# Led_matrix.net
KiCad netlist of a schematic drawn in EAGLE
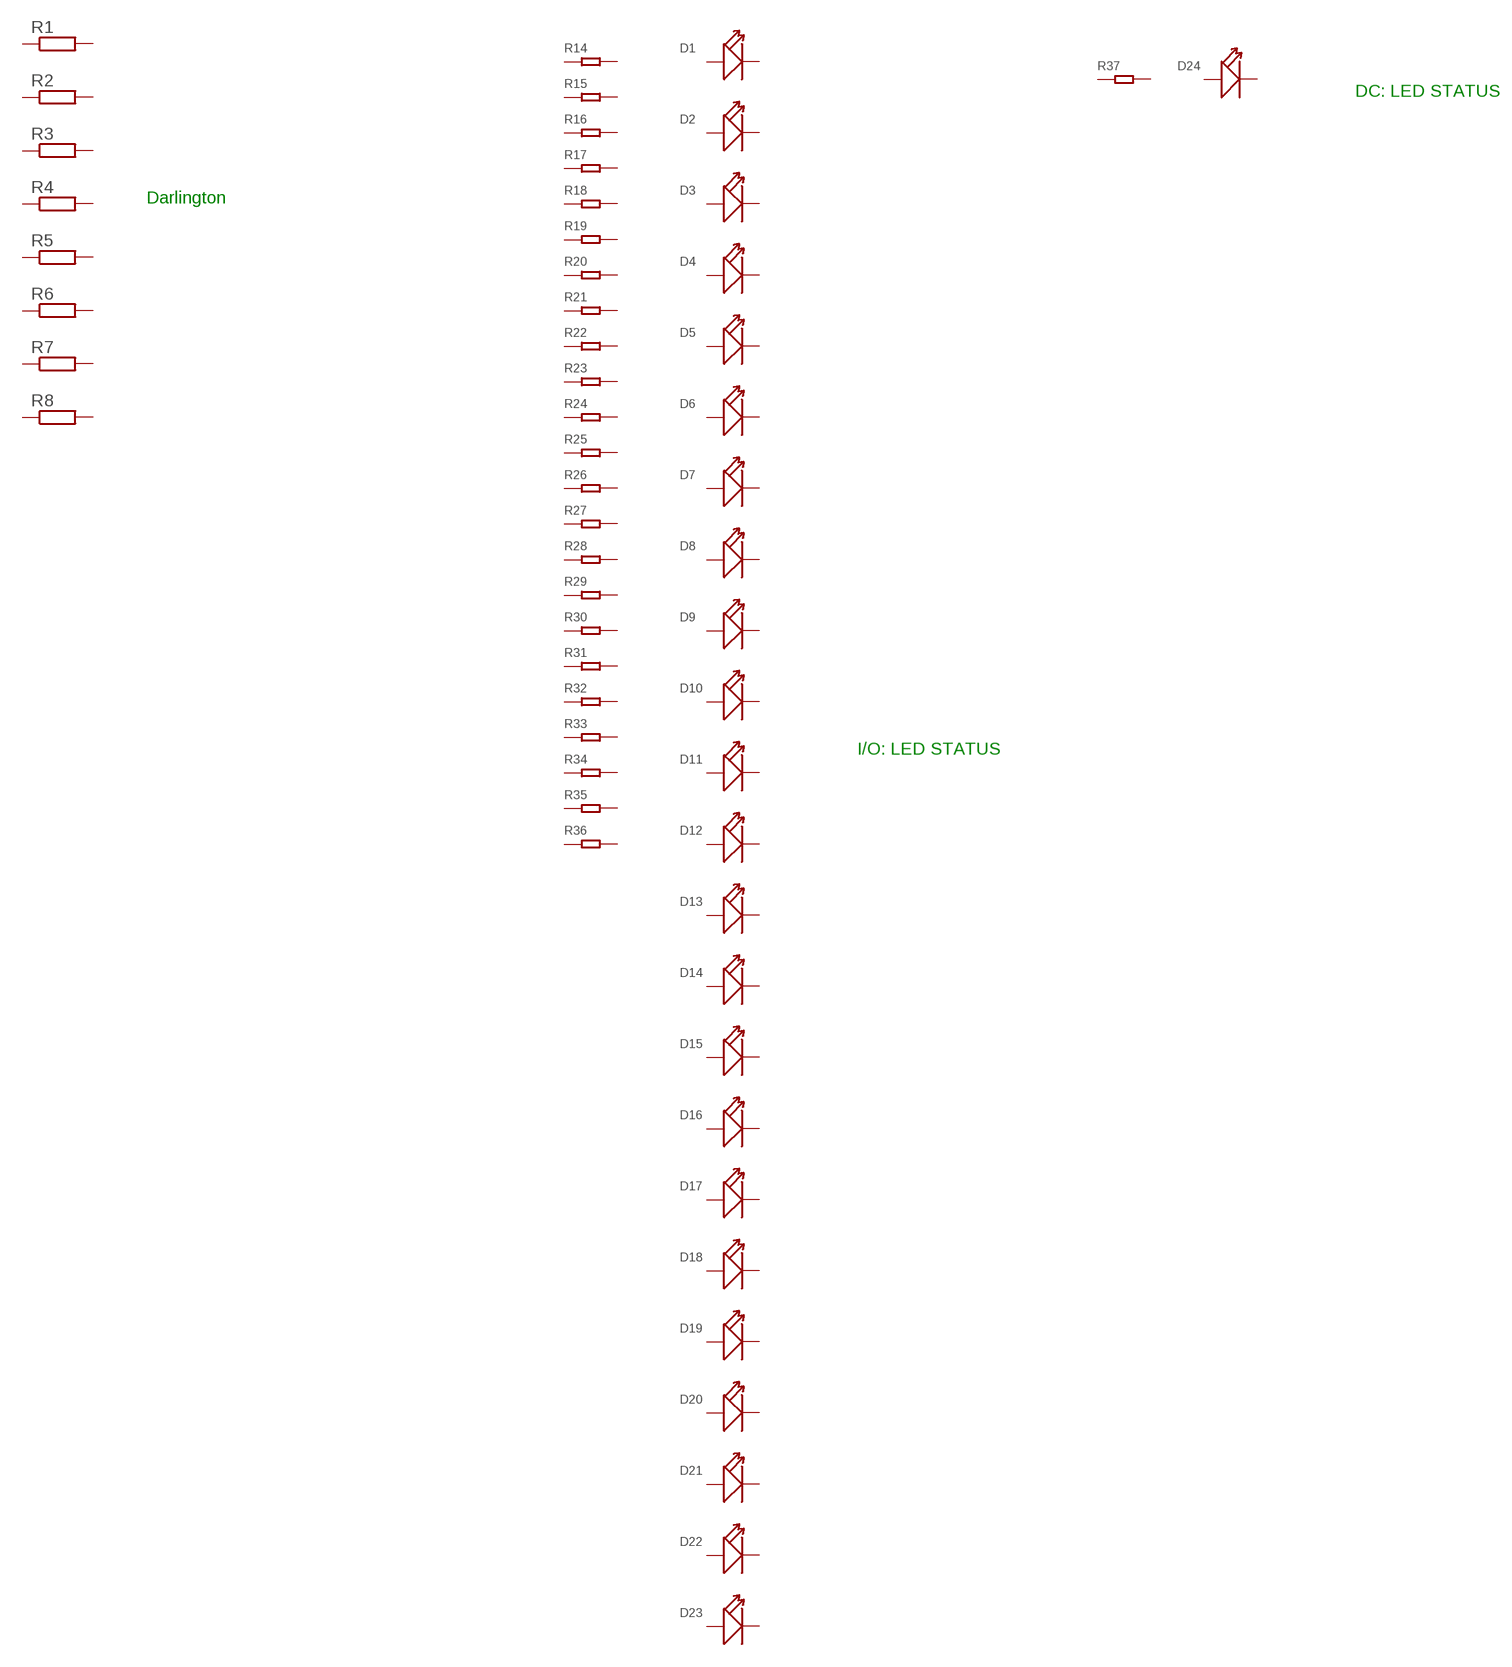
[diagram p0: schematic, sheet 1, part 1 of 2]
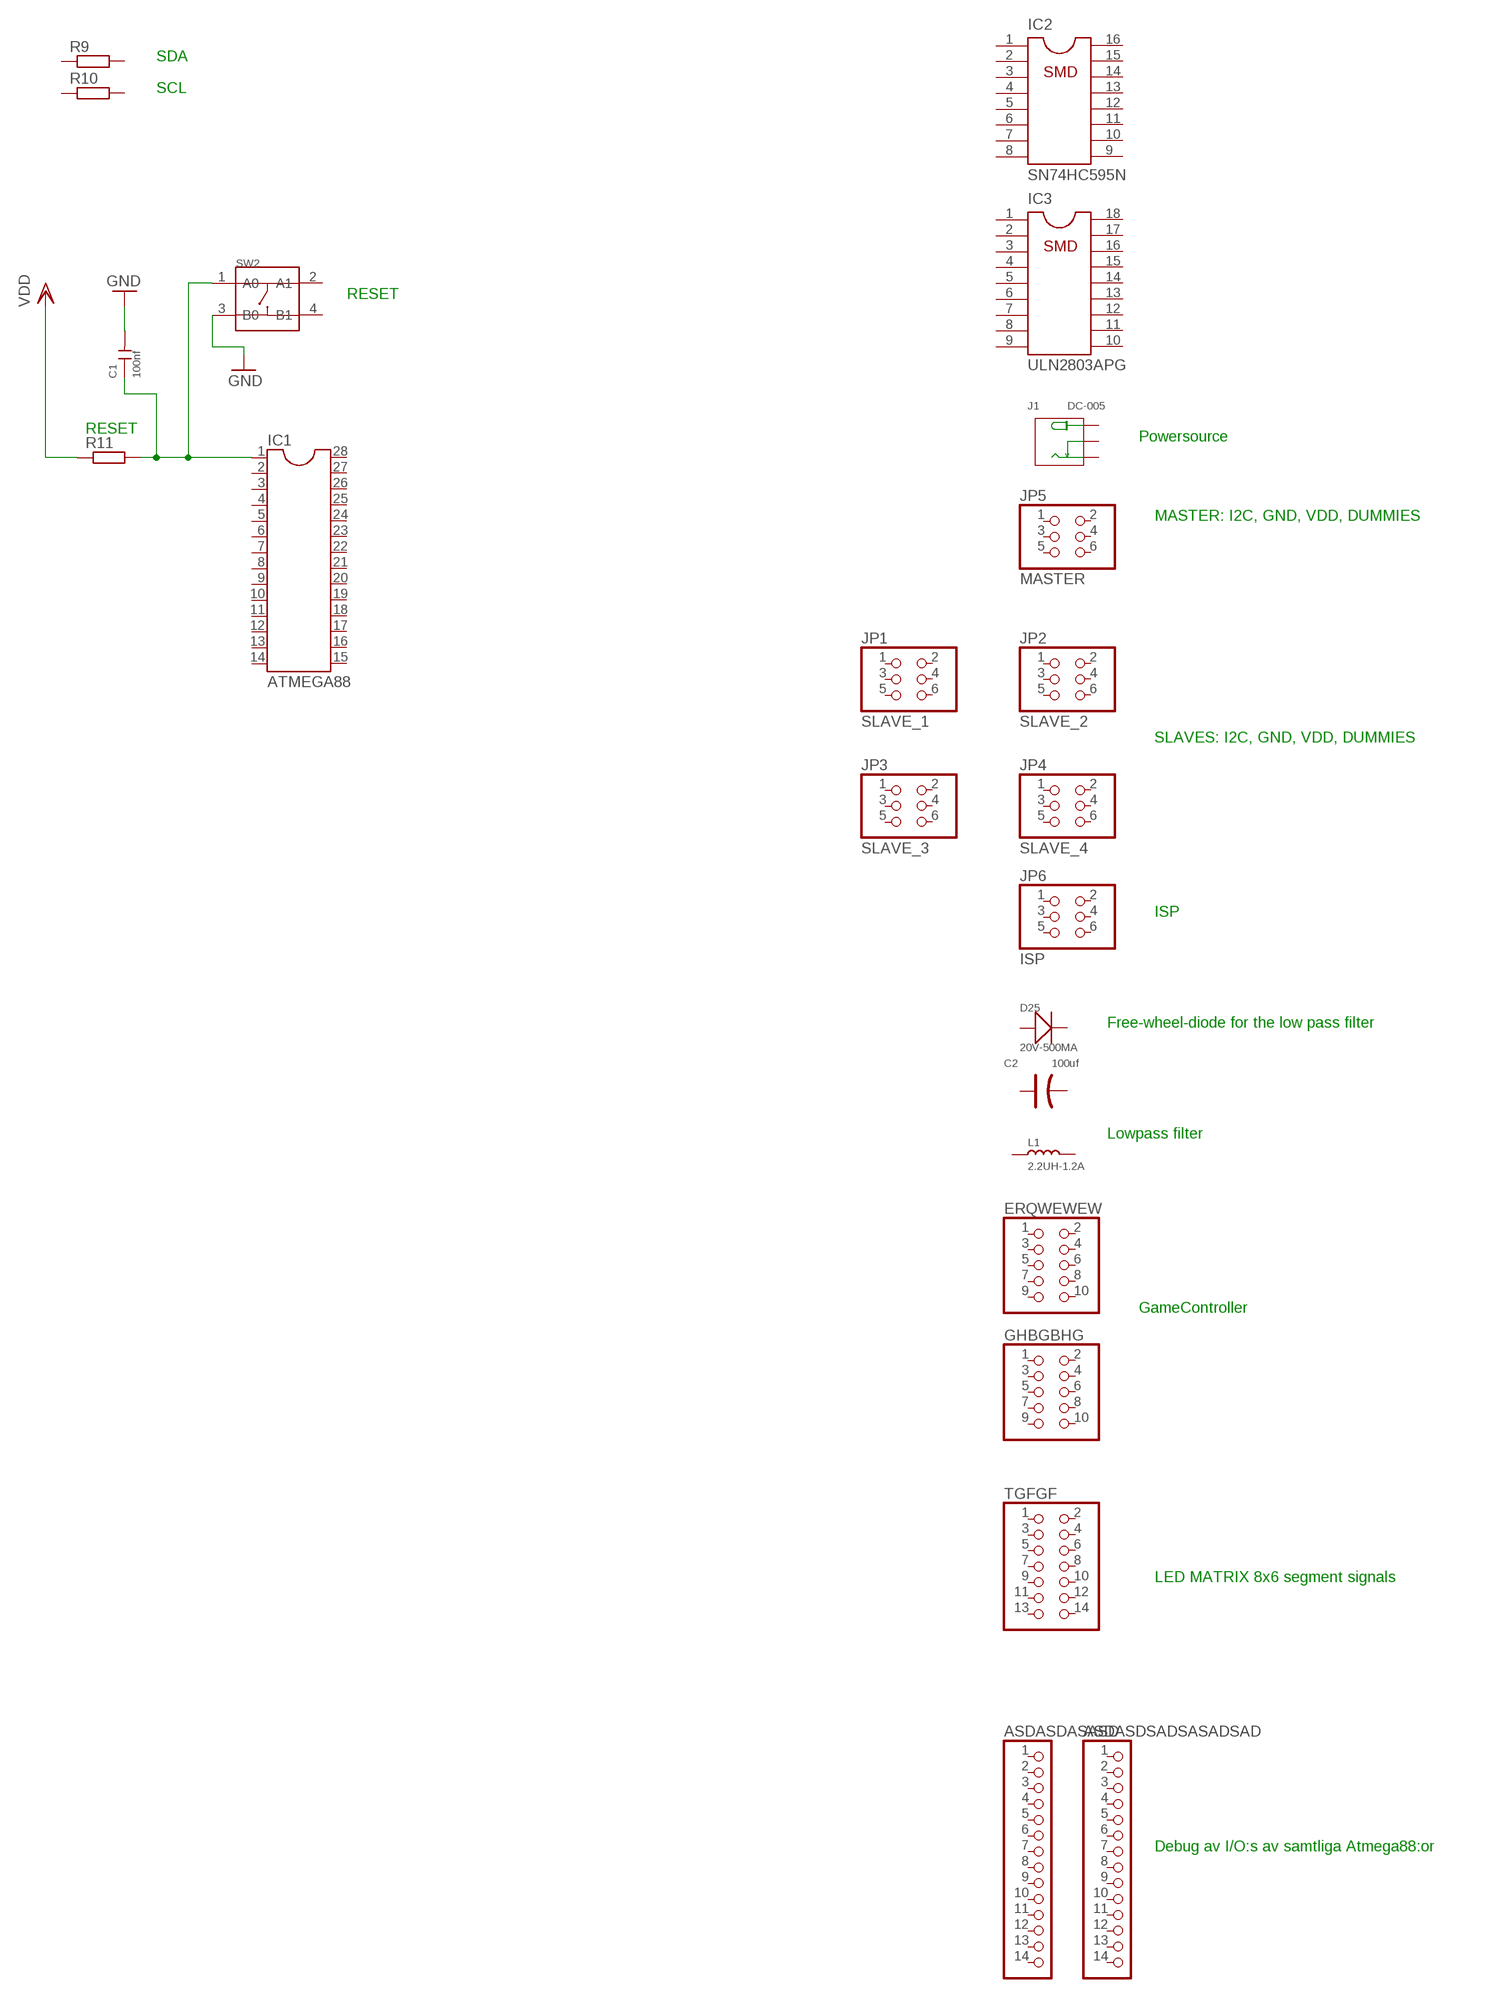
[diagram p1: schematic, sheet 1, part 2 of 2]

(export (version "E")
  (design (tool "Eeschema 10.0.6"))
  (components
    (comp (ref "ASDASDASASD")
      (value "PINHD-1X14")
      (footprint "eagle-import:1X14")
      (libsource (lib "eagle-import") (part "PINHD-1X14"))
    )
    (comp (ref "ASDASDSADSASADSAD")
      (value "PINHD-1X14")
      (footprint "eagle-import:1X14")
      (libsource (lib "eagle-import") (part "PINHD-1X14"))
    )
    (comp (ref "C1")
      (value "100nf")
      (footprint "eagle-import:CERAMIC-2.54")
      (fields (field (name "MPN") "CC1-F5SL2A101KSPW"))
      (libsource (lib "eagle-import") (part "DIP-CERAMIC-DISC-100NF-50V-Y5V(D5.0MM)"))
    )
    (comp (ref "C2")
      (value "100uf")
      (footprint "eagle-import:PC-D5.3MM")
      (libsource (lib "eagle-import") (part "DIP-ALUMINUM-100UF-16V(D5-H7MM)"))
    )
    (comp (ref "D1")
      (value "SMD-LED-CLEAR-GREEN(0603)")
      (footprint "eagle-import:LED-0603")
      (fields (field (name "MPN") "19-217-G7C-AN1P2-3T"))
      (libsource (lib "eagle-import") (part "SMD-LED-CLEAR-GREEN(0603)"))
    )
    (comp (ref "D2")
      (value "SMD-LED-CLEAR-GREEN(0603)")
      (footprint "eagle-import:LED-0603")
      (fields (field (name "MPN") "19-217-G7C-AN1P2-3T"))
      (libsource (lib "eagle-import") (part "SMD-LED-CLEAR-GREEN(0603)"))
    )
    (comp (ref "D3")
      (value "SMD-LED-CLEAR-GREEN(0603)")
      (footprint "eagle-import:LED-0603")
      (fields (field (name "MPN") "19-217-G7C-AN1P2-3T"))
      (libsource (lib "eagle-import") (part "SMD-LED-CLEAR-GREEN(0603)"))
    )
    (comp (ref "D4")
      (value "SMD-LED-CLEAR-GREEN(0603)")
      (footprint "eagle-import:LED-0603")
      (fields (field (name "MPN") "19-217-G7C-AN1P2-3T"))
      (libsource (lib "eagle-import") (part "SMD-LED-CLEAR-GREEN(0603)"))
    )
    (comp (ref "D5")
      (value "SMD-LED-CLEAR-GREEN(0603)")
      (footprint "eagle-import:LED-0603")
      (fields (field (name "MPN") "19-217-G7C-AN1P2-3T"))
      (libsource (lib "eagle-import") (part "SMD-LED-CLEAR-GREEN(0603)"))
    )
    (comp (ref "D6")
      (value "SMD-LED-CLEAR-GREEN(0603)")
      (footprint "eagle-import:LED-0603")
      (fields (field (name "MPN") "19-217-G7C-AN1P2-3T"))
      (libsource (lib "eagle-import") (part "SMD-LED-CLEAR-GREEN(0603)"))
    )
    (comp (ref "D7")
      (value "SMD-LED-CLEAR-GREEN(0603)")
      (footprint "eagle-import:LED-0603")
      (fields (field (name "MPN") "19-217-G7C-AN1P2-3T"))
      (libsource (lib "eagle-import") (part "SMD-LED-CLEAR-GREEN(0603)"))
    )
    (comp (ref "D8")
      (value "SMD-LED-CLEAR-GREEN(0603)")
      (footprint "eagle-import:LED-0603")
      (fields (field (name "MPN") "19-217-G7C-AN1P2-3T"))
      (libsource (lib "eagle-import") (part "SMD-LED-CLEAR-GREEN(0603)"))
    )
    (comp (ref "D9")
      (value "SMD-LED-CLEAR-GREEN(0603)")
      (footprint "eagle-import:LED-0603")
      (fields (field (name "MPN") "19-217-G7C-AN1P2-3T"))
      (libsource (lib "eagle-import") (part "SMD-LED-CLEAR-GREEN(0603)"))
    )
    (comp (ref "D10")
      (value "SMD-LED-CLEAR-GREEN(0603)")
      (footprint "eagle-import:LED-0603")
      (fields (field (name "MPN") "19-217-G7C-AN1P2-3T"))
      (libsource (lib "eagle-import") (part "SMD-LED-CLEAR-GREEN(0603)"))
    )
    (comp (ref "D11")
      (value "SMD-LED-CLEAR-GREEN(0603)")
      (footprint "eagle-import:LED-0603")
      (fields (field (name "MPN") "19-217-G7C-AN1P2-3T"))
      (libsource (lib "eagle-import") (part "SMD-LED-CLEAR-GREEN(0603)"))
    )
    (comp (ref "D12")
      (value "SMD-LED-CLEAR-GREEN(0603)")
      (footprint "eagle-import:LED-0603")
      (fields (field (name "MPN") "19-217-G7C-AN1P2-3T"))
      (libsource (lib "eagle-import") (part "SMD-LED-CLEAR-GREEN(0603)"))
    )
    (comp (ref "D13")
      (value "SMD-LED-CLEAR-GREEN(0603)")
      (footprint "eagle-import:LED-0603")
      (fields (field (name "MPN") "19-217-G7C-AN1P2-3T"))
      (libsource (lib "eagle-import") (part "SMD-LED-CLEAR-GREEN(0603)"))
    )
    (comp (ref "D14")
      (value "SMD-LED-CLEAR-GREEN(0603)")
      (footprint "eagle-import:LED-0603")
      (fields (field (name "MPN") "19-217-G7C-AN1P2-3T"))
      (libsource (lib "eagle-import") (part "SMD-LED-CLEAR-GREEN(0603)"))
    )
    (comp (ref "D15")
      (value "SMD-LED-CLEAR-GREEN(0603)")
      (footprint "eagle-import:LED-0603")
      (fields (field (name "MPN") "19-217-G7C-AN1P2-3T"))
      (libsource (lib "eagle-import") (part "SMD-LED-CLEAR-GREEN(0603)"))
    )
    (comp (ref "D16")
      (value "SMD-LED-CLEAR-GREEN(0603)")
      (footprint "eagle-import:LED-0603")
      (fields (field (name "MPN") "19-217-G7C-AN1P2-3T"))
      (libsource (lib "eagle-import") (part "SMD-LED-CLEAR-GREEN(0603)"))
    )
    (comp (ref "D17")
      (value "SMD-LED-CLEAR-GREEN(0603)")
      (footprint "eagle-import:LED-0603")
      (fields (field (name "MPN") "19-217-G7C-AN1P2-3T"))
      (libsource (lib "eagle-import") (part "SMD-LED-CLEAR-GREEN(0603)"))
    )
    (comp (ref "D18")
      (value "SMD-LED-CLEAR-GREEN(0603)")
      (footprint "eagle-import:LED-0603")
      (fields (field (name "MPN") "19-217-G7C-AN1P2-3T"))
      (libsource (lib "eagle-import") (part "SMD-LED-CLEAR-GREEN(0603)"))
    )
    (comp (ref "D19")
      (value "SMD-LED-CLEAR-GREEN(0603)")
      (footprint "eagle-import:LED-0603")
      (fields (field (name "MPN") "19-217-G7C-AN1P2-3T"))
      (libsource (lib "eagle-import") (part "SMD-LED-CLEAR-GREEN(0603)"))
    )
    (comp (ref "D20")
      (value "SMD-LED-CLEAR-GREEN(0603)")
      (footprint "eagle-import:LED-0603")
      (fields (field (name "MPN") "19-217-G7C-AN1P2-3T"))
      (libsource (lib "eagle-import") (part "SMD-LED-CLEAR-GREEN(0603)"))
    )
    (comp (ref "D21")
      (value "SMD-LED-CLEAR-GREEN(0603)")
      (footprint "eagle-import:LED-0603")
      (fields (field (name "MPN") "19-217-G7C-AN1P2-3T"))
      (libsource (lib "eagle-import") (part "SMD-LED-CLEAR-GREEN(0603)"))
    )
    (comp (ref "D22")
      (value "SMD-LED-CLEAR-GREEN(0603)")
      (footprint "eagle-import:LED-0603")
      (fields (field (name "MPN") "19-217-G7C-AN1P2-3T"))
      (libsource (lib "eagle-import") (part "SMD-LED-CLEAR-GREEN(0603)"))
    )
    (comp (ref "D23")
      (value "SMD-LED-CLEAR-GREEN(0603)")
      (footprint "eagle-import:LED-0603")
      (fields (field (name "MPN") "19-217-G7C-AN1P2-3T"))
      (libsource (lib "eagle-import") (part "SMD-LED-CLEAR-GREEN(0603)"))
    )
    (comp (ref "D24")
      (value "SMD-LED-CLEAR-GREEN(0603)")
      (footprint "eagle-import:LED-0603")
      (fields (field (name "MPN") "19-217-G7C-AN1P2-3T"))
      (libsource (lib "eagle-import") (part "SMD-LED-CLEAR-GREEN(0603)"))
    )
    (comp (ref "D25")
      (value "20V-500MA")
      (footprint "eagle-import:SOD-123")
      (fields (field (name "MPN") "SS0520-7-F"))
      (libsource (lib "eagle-import") (part "SMD-DIODE-SCHOTTKY-20V-500MA(SOD-123)P"))
    )
    (comp (ref "ERQWEWEW")
      (value "PINHD-2X5")
      (footprint "eagle-import:2X05")
      (libsource (lib "eagle-import") (part "PINHD-2X5"))
    )
    (comp (ref "GHBGBHG")
      (value "PINHD-2X5")
      (footprint "eagle-import:2X05")
      (libsource (lib "eagle-import") (part "PINHD-2X5"))
    )
    (comp (ref "IC1")
      (value "ATMEGA88")
      (footprint "eagle-import:DIL28-3")
      (libsource (lib "eagle-import") (part "DIL28-3"))
    )
    (comp (ref "IC2")
      (value "SN74HC595N")
      (footprint "eagle-import:DIL16-SMD")
      (libsource (lib "eagle-import") (part "DIL16-SMD"))
    )
    (comp (ref "IC3")
      (value "ULN2803APG")
      (footprint "eagle-import:DIL18-SMD")
      (libsource (lib "eagle-import") (part "DIL18-SMD"))
    )
    (comp (ref "J1")
      (value "DC-005")
      (footprint "eagle-import:DCJ3P-14.2X11.0X9.0MM")
      (libsource (lib "eagle-import") (part "CONN-POWER-JACK-2.1MM(DC-005)"))
    )
    (comp (ref "JP1")
      (value "SLAVE_1")
      (footprint "eagle-import:2X03-SMD")
      (libsource (lib "eagle-import") (part "PINHD-2X3-SMD"))
    )
    (comp (ref "JP2")
      (value "SLAVE_2")
      (footprint "eagle-import:2X03-SMD")
      (libsource (lib "eagle-import") (part "PINHD-2X3-SMD"))
    )
    (comp (ref "JP3")
      (value "SLAVE_3")
      (footprint "eagle-import:2X03-SMD")
      (libsource (lib "eagle-import") (part "PINHD-2X3-SMD"))
    )
    (comp (ref "JP4")
      (value "SLAVE_4")
      (footprint "eagle-import:2X03-SMD")
      (libsource (lib "eagle-import") (part "PINHD-2X3-SMD"))
    )
    (comp (ref "JP5")
      (value "MASTER")
      (footprint "eagle-import:2X03-SMD")
      (libsource (lib "eagle-import") (part "PINHD-2X3-SMD"))
    )
    (comp (ref "JP6")
      (value "ISP")
      (footprint "eagle-import:2X03-SHROUDED")
      (libsource (lib "eagle-import") (part "PINHD-2X3-SHROUDED"))
    )
    (comp (ref "L1")
      (value "2.2UH-1.2A")
      (footprint "eagle-import:L0805")
      (fields (field (name "MPN") "LQM2MPN2R2MG0"))
      (libsource (lib "eagle-import") (part "SMD-INDUCTOR-2.2UH-20%-1.2A(0805)"))
    )
    (comp (ref "R1")
      (value "R-EU_0411/15")
      (footprint "eagle-import:0411_15")
      (libsource (lib "eagle-import") (part "R-EU_0411/15"))
    )
    (comp (ref "R2")
      (value "R-EU_0411/15")
      (footprint "eagle-import:0411_15")
      (libsource (lib "eagle-import") (part "R-EU_0411/15"))
    )
    (comp (ref "R3")
      (value "R-EU_0411/15")
      (footprint "eagle-import:0411_15")
      (libsource (lib "eagle-import") (part "R-EU_0411/15"))
    )
    (comp (ref "R4")
      (value "R-EU_0411/15")
      (footprint "eagle-import:0411_15")
      (libsource (lib "eagle-import") (part "R-EU_0411/15"))
    )
    (comp (ref "R5")
      (value "R-EU_0411/15")
      (footprint "eagle-import:0411_15")
      (libsource (lib "eagle-import") (part "R-EU_0411/15"))
    )
    (comp (ref "R6")
      (value "R-EU_0411/15")
      (footprint "eagle-import:0411_15")
      (libsource (lib "eagle-import") (part "R-EU_0411/15"))
    )
    (comp (ref "R7")
      (value "R-EU_0411/15")
      (footprint "eagle-import:0411_15")
      (libsource (lib "eagle-import") (part "R-EU_0411/15"))
    )
    (comp (ref "R8")
      (value "R-EU_0411/15")
      (footprint "eagle-import:0411_15")
      (libsource (lib "eagle-import") (part "R-EU_0411/15"))
    )
    (comp (ref "R9")
      (value "R-EU_0207/10")
      (footprint "eagle-import:0207_10")
      (libsource (lib "eagle-import") (part "R-EU_0207/10"))
    )
    (comp (ref "R10")
      (value "R-EU_0207/10")
      (footprint "eagle-import:0207_10")
      (libsource (lib "eagle-import") (part "R-EU_0207/10"))
    )
    (comp (ref "R11")
      (value "R-EU_0207/10")
      (footprint "eagle-import:0207_10")
      (libsource (lib "eagle-import") (part "R-EU_0207/10"))
    )
    (comp (ref "R14")
      (value "SMD-RES-100R-5%-1/10W(0603)")
      (footprint "eagle-import:R0603")
      (fields (field (name "MPN") "RC0603JR-07100RL"))
      (libsource (lib "eagle-import") (part "SMD-RES-100R-5%-1/10W(0603)"))
    )
    (comp (ref "R15")
      (value "SMD-RES-100R-5%-1/10W(0603)")
      (footprint "eagle-import:R0603")
      (fields (field (name "MPN") "RC0603JR-07100RL"))
      (libsource (lib "eagle-import") (part "SMD-RES-100R-5%-1/10W(0603)"))
    )
    (comp (ref "R16")
      (value "SMD-RES-100R-5%-1/10W(0603)")
      (footprint "eagle-import:R0603")
      (fields (field (name "MPN") "RC0603JR-07100RL"))
      (libsource (lib "eagle-import") (part "SMD-RES-100R-5%-1/10W(0603)"))
    )
    (comp (ref "R17")
      (value "SMD-RES-100R-5%-1/10W(0603)")
      (footprint "eagle-import:R0603")
      (fields (field (name "MPN") "RC0603JR-07100RL"))
      (libsource (lib "eagle-import") (part "SMD-RES-100R-5%-1/10W(0603)"))
    )
    (comp (ref "R18")
      (value "SMD-RES-100R-5%-1/10W(0603)")
      (footprint "eagle-import:R0603")
      (fields (field (name "MPN") "RC0603JR-07100RL"))
      (libsource (lib "eagle-import") (part "SMD-RES-100R-5%-1/10W(0603)"))
    )
    (comp (ref "R19")
      (value "SMD-RES-100R-5%-1/10W(0603)")
      (footprint "eagle-import:R0603")
      (fields (field (name "MPN") "RC0603JR-07100RL"))
      (libsource (lib "eagle-import") (part "SMD-RES-100R-5%-1/10W(0603)"))
    )
    (comp (ref "R20")
      (value "SMD-RES-100R-5%-1/10W(0603)")
      (footprint "eagle-import:R0603")
      (fields (field (name "MPN") "RC0603JR-07100RL"))
      (libsource (lib "eagle-import") (part "SMD-RES-100R-5%-1/10W(0603)"))
    )
    (comp (ref "R21")
      (value "SMD-RES-100R-5%-1/10W(0603)")
      (footprint "eagle-import:R0603")
      (fields (field (name "MPN") "RC0603JR-07100RL"))
      (libsource (lib "eagle-import") (part "SMD-RES-100R-5%-1/10W(0603)"))
    )
    (comp (ref "R22")
      (value "SMD-RES-100R-5%-1/10W(0603)")
      (footprint "eagle-import:R0603")
      (fields (field (name "MPN") "RC0603JR-07100RL"))
      (libsource (lib "eagle-import") (part "SMD-RES-100R-5%-1/10W(0603)"))
    )
    (comp (ref "R23")
      (value "SMD-RES-100R-5%-1/10W(0603)")
      (footprint "eagle-import:R0603")
      (fields (field (name "MPN") "RC0603JR-07100RL"))
      (libsource (lib "eagle-import") (part "SMD-RES-100R-5%-1/10W(0603)"))
    )
    (comp (ref "R24")
      (value "SMD-RES-100R-5%-1/10W(0603)")
      (footprint "eagle-import:R0603")
      (fields (field (name "MPN") "RC0603JR-07100RL"))
      (libsource (lib "eagle-import") (part "SMD-RES-100R-5%-1/10W(0603)"))
    )
    (comp (ref "R25")
      (value "SMD-RES-100R-5%-1/10W(0603)")
      (footprint "eagle-import:R0603")
      (fields (field (name "MPN") "RC0603JR-07100RL"))
      (libsource (lib "eagle-import") (part "SMD-RES-100R-5%-1/10W(0603)"))
    )
    (comp (ref "R26")
      (value "SMD-RES-100R-5%-1/10W(0603)")
      (footprint "eagle-import:R0603")
      (fields (field (name "MPN") "RC0603JR-07100RL"))
      (libsource (lib "eagle-import") (part "SMD-RES-100R-5%-1/10W(0603)"))
    )
    (comp (ref "R27")
      (value "SMD-RES-100R-5%-1/10W(0603)")
      (footprint "eagle-import:R0603")
      (fields (field (name "MPN") "RC0603JR-07100RL"))
      (libsource (lib "eagle-import") (part "SMD-RES-100R-5%-1/10W(0603)"))
    )
    (comp (ref "R28")
      (value "SMD-RES-100R-5%-1/10W(0603)")
      (footprint "eagle-import:R0603")
      (fields (field (name "MPN") "RC0603JR-07100RL"))
      (libsource (lib "eagle-import") (part "SMD-RES-100R-5%-1/10W(0603)"))
    )
    (comp (ref "R29")
      (value "SMD-RES-100R-5%-1/10W(0603)")
      (footprint "eagle-import:R0603")
      (fields (field (name "MPN") "RC0603JR-07100RL"))
      (libsource (lib "eagle-import") (part "SMD-RES-100R-5%-1/10W(0603)"))
    )
    (comp (ref "R30")
      (value "SMD-RES-100R-5%-1/10W(0603)")
      (footprint "eagle-import:R0603")
      (fields (field (name "MPN") "RC0603JR-07100RL"))
      (libsource (lib "eagle-import") (part "SMD-RES-100R-5%-1/10W(0603)"))
    )
    (comp (ref "R31")
      (value "SMD-RES-100R-5%-1/10W(0603)")
      (footprint "eagle-import:R0603")
      (fields (field (name "MPN") "RC0603JR-07100RL"))
      (libsource (lib "eagle-import") (part "SMD-RES-100R-5%-1/10W(0603)"))
    )
    (comp (ref "R32")
      (value "SMD-RES-100R-5%-1/10W(0603)")
      (footprint "eagle-import:R0603")
      (fields (field (name "MPN") "RC0603JR-07100RL"))
      (libsource (lib "eagle-import") (part "SMD-RES-100R-5%-1/10W(0603)"))
    )
    (comp (ref "R33")
      (value "SMD-RES-100R-5%-1/10W(0603)")
      (footprint "eagle-import:R0603")
      (fields (field (name "MPN") "RC0603JR-07100RL"))
      (libsource (lib "eagle-import") (part "SMD-RES-100R-5%-1/10W(0603)"))
    )
    (comp (ref "R34")
      (value "SMD-RES-100R-5%-1/10W(0603)")
      (footprint "eagle-import:R0603")
      (fields (field (name "MPN") "RC0603JR-07100RL"))
      (libsource (lib "eagle-import") (part "SMD-RES-100R-5%-1/10W(0603)"))
    )
    (comp (ref "R35")
      (value "SMD-RES-100R-5%-1/10W(0603)")
      (footprint "eagle-import:R0603")
      (fields (field (name "MPN") "RC0603JR-07100RL"))
      (libsource (lib "eagle-import") (part "SMD-RES-100R-5%-1/10W(0603)"))
    )
    (comp (ref "R36")
      (value "SMD-RES-100R-5%-1/10W(0603)")
      (footprint "eagle-import:R0603")
      (fields (field (name "MPN") "RC0603JR-07100RL"))
      (libsource (lib "eagle-import") (part "SMD-RES-100R-5%-1/10W(0603)"))
    )
    (comp (ref "R37")
      (value "SMD-RES-100R-5%-1/10W(0603)")
      (footprint "eagle-import:R0603")
      (fields (field (name "MPN") "RC0603JR-07100RL"))
      (libsource (lib "eagle-import") (part "SMD-RES-100R-5%-1/10W(0603)"))
    )
    (comp (ref "SW2")
      (value "SMD-BUTTON(4P-6.0X6.0X7.5MM)")
      (footprint "eagle-import:SW4-4.5-6.0X6.0X7.5MM")
      (libsource (lib "eagle-import") (part "SMD-BUTTON(4P-6.0X6.0X7.5MM)"))
    )
    (comp (ref "TGFGF")
      (value "PINHD-2X7")
      (footprint "eagle-import:2X07")
      (libsource (lib "eagle-import") (part "PINHD-2X7"))
    )
  )
  (nets
    (net (code "1") (name "GND") (class "Default")
      (node (ref "C1") (pin "2") (pinfunction "2_2") (pintype "passive"))
      (node (ref "SW2") (pin "3") (pinfunction "B0_3") (pintype "bidirectional"))
    )
    (net (code "2") (name "Net-(SW2-A0)") (class "Default")
      (node (ref "C1") (pin "1") (pinfunction "1_1") (pintype "passive"))
      (node (ref "IC1") (pin "1") (pinfunction "1_1") (pintype "passive"))
      (node (ref "R11") (pin "2") (pinfunction "2_2") (pintype "passive"))
      (node (ref "SW2") (pin "1") (pinfunction "A0_1") (pintype "bidirectional"))
    )
    (net (code "3") (name "VDD") (class "Default")
      (node (ref "R11") (pin "1") (pinfunction "1_1") (pintype "passive"))
    )
    (net (code "4") (name "unconnected-(ASDASDASASD-Pad1)") (class "Default")
      (node (ref "ASDASDASASD") (pin "1") (pinfunction "1_1") (pintype "passive"))
    )
    (net (code "5") (name "unconnected-(ASDASDASASD-Pad2)") (class "Default")
      (node (ref "ASDASDASASD") (pin "2") (pinfunction "2_2") (pintype "passive"))
    )
    (net (code "6") (name "unconnected-(ASDASDASASD-Pad3)") (class "Default")
      (node (ref "ASDASDASASD") (pin "3") (pinfunction "3_3") (pintype "passive"))
    )
    (net (code "7") (name "unconnected-(ASDASDASASD-Pad4)") (class "Default")
      (node (ref "ASDASDASASD") (pin "4") (pinfunction "4_4") (pintype "passive"))
    )
    (net (code "8") (name "unconnected-(ASDASDASASD-Pad5)") (class "Default")
      (node (ref "ASDASDASASD") (pin "5") (pinfunction "5_5") (pintype "passive"))
    )
    (net (code "9") (name "unconnected-(ASDASDASASD-Pad6)") (class "Default")
      (node (ref "ASDASDASASD") (pin "6") (pinfunction "6_6") (pintype "passive"))
    )
    (net (code "10") (name "unconnected-(ASDASDASASD-Pad7)") (class "Default")
      (node (ref "ASDASDASASD") (pin "7") (pinfunction "7_7") (pintype "passive"))
    )
    (net (code "11") (name "unconnected-(ASDASDASASD-Pad8)") (class "Default")
      (node (ref "ASDASDASASD") (pin "8") (pinfunction "8_8") (pintype "passive"))
    )
    (net (code "12") (name "unconnected-(ASDASDASASD-Pad9)") (class "Default")
      (node (ref "ASDASDASASD") (pin "9") (pinfunction "9_9") (pintype "passive"))
    )
    (net (code "13") (name "unconnected-(ASDASDASASD-Pad10)") (class "Default")
      (node (ref "ASDASDASASD") (pin "10") (pinfunction "10_10") (pintype "passive"))
    )
    (net (code "14") (name "unconnected-(ASDASDASASD-Pad11)") (class "Default")
      (node (ref "ASDASDASASD") (pin "11") (pinfunction "11_11") (pintype "passive"))
    )
    (net (code "15") (name "unconnected-(ASDASDASASD-Pad12)") (class "Default")
      (node (ref "ASDASDASASD") (pin "12") (pinfunction "12_12") (pintype "passive"))
    )
    (net (code "16") (name "unconnected-(ASDASDASASD-Pad13)") (class "Default")
      (node (ref "ASDASDASASD") (pin "13") (pinfunction "13_13") (pintype "passive"))
    )
    (net (code "17") (name "unconnected-(ASDASDASASD-Pad14)") (class "Default")
      (node (ref "ASDASDASASD") (pin "14") (pinfunction "14_14") (pintype "passive"))
    )
    (net (code "18") (name "unconnected-(ASDASDSADSASADSAD-Pad1)") (class "Default")
      (node (ref "ASDASDSADSASADSAD") (pin "1") (pinfunction "1_1") (pintype "passive"))
    )
    (net (code "19") (name "unconnected-(ASDASDSADSASADSAD-Pad2)") (class "Default")
      (node (ref "ASDASDSADSASADSAD") (pin "2") (pinfunction "2_2") (pintype "passive"))
    )
    (net (code "20") (name "unconnected-(ASDASDSADSASADSAD-Pad3)") (class "Default")
      (node (ref "ASDASDSADSASADSAD") (pin "3") (pinfunction "3_3") (pintype "passive"))
    )
    (net (code "21") (name "unconnected-(ASDASDSADSASADSAD-Pad4)") (class "Default")
      (node (ref "ASDASDSADSASADSAD") (pin "4") (pinfunction "4_4") (pintype "passive"))
    )
    (net (code "22") (name "unconnected-(ASDASDSADSASADSAD-Pad5)") (class "Default")
      (node (ref "ASDASDSADSASADSAD") (pin "5") (pinfunction "5_5") (pintype "passive"))
    )
    (net (code "23") (name "unconnected-(ASDASDSADSASADSAD-Pad6)") (class "Default")
      (node (ref "ASDASDSADSASADSAD") (pin "6") (pinfunction "6_6") (pintype "passive"))
    )
    (net (code "24") (name "unconnected-(ASDASDSADSASADSAD-Pad7)") (class "Default")
      (node (ref "ASDASDSADSASADSAD") (pin "7") (pinfunction "7_7") (pintype "passive"))
    )
    (net (code "25") (name "unconnected-(ASDASDSADSASADSAD-Pad8)") (class "Default")
      (node (ref "ASDASDSADSASADSAD") (pin "8") (pinfunction "8_8") (pintype "passive"))
    )
    (net (code "26") (name "unconnected-(ASDASDSADSASADSAD-Pad9)") (class "Default")
      (node (ref "ASDASDSADSASADSAD") (pin "9") (pinfunction "9_9") (pintype "passive"))
    )
    (net (code "27") (name "unconnected-(ASDASDSADSASADSAD-Pad10)") (class "Default")
      (node (ref "ASDASDSADSASADSAD") (pin "10") (pinfunction "10_10") (pintype "passive"))
    )
    (net (code "28") (name "unconnected-(ASDASDSADSASADSAD-Pad11)") (class "Default")
      (node (ref "ASDASDSADSASADSAD") (pin "11") (pinfunction "11_11") (pintype "passive"))
    )
    (net (code "29") (name "unconnected-(ASDASDSADSASADSAD-Pad12)") (class "Default")
      (node (ref "ASDASDSADSASADSAD") (pin "12") (pinfunction "12_12") (pintype "passive"))
    )
    (net (code "30") (name "unconnected-(ASDASDSADSASADSAD-Pad13)") (class "Default")
      (node (ref "ASDASDSADSASADSAD") (pin "13") (pinfunction "13_13") (pintype "passive"))
    )
    (net (code "31") (name "unconnected-(ASDASDSADSASADSAD-Pad14)") (class "Default")
      (node (ref "ASDASDSADSASADSAD") (pin "14") (pinfunction "14_14") (pintype "passive"))
    )
    (net (code "32") (name "unconnected-(C2-Pad+)") (class "Default")
      (node (ref "C2") (pin "+") (pinfunction "+_+") (pintype "passive"))
    )
    (net (code "33") (name "unconnected-(C2-Pad-)") (class "Default")
      (node (ref "C2") (pin "-") (pinfunction "-_-") (pintype "passive"))
    )
    (net (code "34") (name "unconnected-(D1-Pad+)") (class "Default")
      (node (ref "D1") (pin "+") (pinfunction "+_+") (pintype "passive"))
    )
    (net (code "35") (name "unconnected-(D1-Pad-)") (class "Default")
      (node (ref "D1") (pin "-") (pinfunction "-_-") (pintype "passive"))
    )
    (net (code "36") (name "unconnected-(D2-Pad+)") (class "Default")
      (node (ref "D2") (pin "+") (pinfunction "+_+") (pintype "passive"))
    )
    (net (code "37") (name "unconnected-(D2-Pad-)") (class "Default")
      (node (ref "D2") (pin "-") (pinfunction "-_-") (pintype "passive"))
    )
    (net (code "38") (name "unconnected-(D3-Pad+)") (class "Default")
      (node (ref "D3") (pin "+") (pinfunction "+_+") (pintype "passive"))
    )
    (net (code "39") (name "unconnected-(D3-Pad-)") (class "Default")
      (node (ref "D3") (pin "-") (pinfunction "-_-") (pintype "passive"))
    )
    (net (code "40") (name "unconnected-(D4-Pad+)") (class "Default")
      (node (ref "D4") (pin "+") (pinfunction "+_+") (pintype "passive"))
    )
    (net (code "41") (name "unconnected-(D4-Pad-)") (class "Default")
      (node (ref "D4") (pin "-") (pinfunction "-_-") (pintype "passive"))
    )
    (net (code "42") (name "unconnected-(D5-Pad+)") (class "Default")
      (node (ref "D5") (pin "+") (pinfunction "+_+") (pintype "passive"))
    )
    (net (code "43") (name "unconnected-(D5-Pad-)") (class "Default")
      (node (ref "D5") (pin "-") (pinfunction "-_-") (pintype "passive"))
    )
    (net (code "44") (name "unconnected-(D6-Pad+)") (class "Default")
      (node (ref "D6") (pin "+") (pinfunction "+_+") (pintype "passive"))
    )
    (net (code "45") (name "unconnected-(D6-Pad-)") (class "Default")
      (node (ref "D6") (pin "-") (pinfunction "-_-") (pintype "passive"))
    )
    (net (code "46") (name "unconnected-(D7-Pad+)") (class "Default")
      (node (ref "D7") (pin "+") (pinfunction "+_+") (pintype "passive"))
    )
    (net (code "47") (name "unconnected-(D7-Pad-)") (class "Default")
      (node (ref "D7") (pin "-") (pinfunction "-_-") (pintype "passive"))
    )
    (net (code "48") (name "unconnected-(D8-Pad+)") (class "Default")
      (node (ref "D8") (pin "+") (pinfunction "+_+") (pintype "passive"))
    )
    (net (code "49") (name "unconnected-(D8-Pad-)") (class "Default")
      (node (ref "D8") (pin "-") (pinfunction "-_-") (pintype "passive"))
    )
    (net (code "50") (name "unconnected-(D9-Pad+)") (class "Default")
      (node (ref "D9") (pin "+") (pinfunction "+_+") (pintype "passive"))
    )
    (net (code "51") (name "unconnected-(D9-Pad-)") (class "Default")
      (node (ref "D9") (pin "-") (pinfunction "-_-") (pintype "passive"))
    )
    (net (code "52") (name "unconnected-(D10-Pad+)") (class "Default")
      (node (ref "D10") (pin "+") (pinfunction "+_+") (pintype "passive"))
    )
    (net (code "53") (name "unconnected-(D10-Pad-)") (class "Default")
      (node (ref "D10") (pin "-") (pinfunction "-_-") (pintype "passive"))
    )
    (net (code "54") (name "unconnected-(D11-Pad+)") (class "Default")
      (node (ref "D11") (pin "+") (pinfunction "+_+") (pintype "passive"))
    )
    (net (code "55") (name "unconnected-(D11-Pad-)") (class "Default")
      (node (ref "D11") (pin "-") (pinfunction "-_-") (pintype "passive"))
    )
    (net (code "56") (name "unconnected-(D12-Pad+)") (class "Default")
      (node (ref "D12") (pin "+") (pinfunction "+_+") (pintype "passive"))
    )
    (net (code "57") (name "unconnected-(D12-Pad-)") (class "Default")
      (node (ref "D12") (pin "-") (pinfunction "-_-") (pintype "passive"))
    )
    (net (code "58") (name "unconnected-(D13-Pad+)") (class "Default")
      (node (ref "D13") (pin "+") (pinfunction "+_+") (pintype "passive"))
    )
    (net (code "59") (name "unconnected-(D13-Pad-)") (class "Default")
      (node (ref "D13") (pin "-") (pinfunction "-_-") (pintype "passive"))
    )
    (net (code "60") (name "unconnected-(D14-Pad+)") (class "Default")
      (node (ref "D14") (pin "+") (pinfunction "+_+") (pintype "passive"))
    )
    (net (code "61") (name "unconnected-(D14-Pad-)") (class "Default")
      (node (ref "D14") (pin "-") (pinfunction "-_-") (pintype "passive"))
    )
    (net (code "62") (name "unconnected-(D15-Pad+)") (class "Default")
      (node (ref "D15") (pin "+") (pinfunction "+_+") (pintype "passive"))
    )
    (net (code "63") (name "unconnected-(D15-Pad-)") (class "Default")
      (node (ref "D15") (pin "-") (pinfunction "-_-") (pintype "passive"))
    )
    (net (code "64") (name "unconnected-(D16-Pad+)") (class "Default")
      (node (ref "D16") (pin "+") (pinfunction "+_+") (pintype "passive"))
    )
    (net (code "65") (name "unconnected-(D16-Pad-)") (class "Default")
      (node (ref "D16") (pin "-") (pinfunction "-_-") (pintype "passive"))
    )
    (net (code "66") (name "unconnected-(D17-Pad+)") (class "Default")
      (node (ref "D17") (pin "+") (pinfunction "+_+") (pintype "passive"))
    )
    (net (code "67") (name "unconnected-(D17-Pad-)") (class "Default")
      (node (ref "D17") (pin "-") (pinfunction "-_-") (pintype "passive"))
    )
    (net (code "68") (name "unconnected-(D18-Pad+)") (class "Default")
      (node (ref "D18") (pin "+") (pinfunction "+_+") (pintype "passive"))
    )
    (net (code "69") (name "unconnected-(D18-Pad-)") (class "Default")
      (node (ref "D18") (pin "-") (pinfunction "-_-") (pintype "passive"))
    )
    (net (code "70") (name "unconnected-(D19-Pad+)") (class "Default")
      (node (ref "D19") (pin "+") (pinfunction "+_+") (pintype "passive"))
    )
    (net (code "71") (name "unconnected-(D19-Pad-)") (class "Default")
      (node (ref "D19") (pin "-") (pinfunction "-_-") (pintype "passive"))
    )
    (net (code "72") (name "unconnected-(D20-Pad+)") (class "Default")
      (node (ref "D20") (pin "+") (pinfunction "+_+") (pintype "passive"))
    )
    (net (code "73") (name "unconnected-(D20-Pad-)") (class "Default")
      (node (ref "D20") (pin "-") (pinfunction "-_-") (pintype "passive"))
    )
    (net (code "74") (name "unconnected-(D21-Pad+)") (class "Default")
      (node (ref "D21") (pin "+") (pinfunction "+_+") (pintype "passive"))
    )
    (net (code "75") (name "unconnected-(D21-Pad-)") (class "Default")
      (node (ref "D21") (pin "-") (pinfunction "-_-") (pintype "passive"))
    )
    (net (code "76") (name "unconnected-(D22-Pad+)") (class "Default")
      (node (ref "D22") (pin "+") (pinfunction "+_+") (pintype "passive"))
    )
    (net (code "77") (name "unconnected-(D22-Pad-)") (class "Default")
      (node (ref "D22") (pin "-") (pinfunction "-_-") (pintype "passive"))
    )
    (net (code "78") (name "unconnected-(D23-Pad+)") (class "Default")
      (node (ref "D23") (pin "+") (pinfunction "+_+") (pintype "passive"))
    )
    (net (code "79") (name "unconnected-(D23-Pad-)") (class "Default")
      (node (ref "D23") (pin "-") (pinfunction "-_-") (pintype "passive"))
    )
    (net (code "80") (name "unconnected-(D24-Pad+)") (class "Default")
      (node (ref "D24") (pin "+") (pinfunction "+_+") (pintype "passive"))
    )
    (net (code "81") (name "unconnected-(D24-Pad-)") (class "Default")
      (node (ref "D24") (pin "-") (pinfunction "-_-") (pintype "passive"))
    )
    (net (code "82") (name "unconnected-(D25-Pad+)") (class "Default")
      (node (ref "D25") (pin "+") (pinfunction "+_+") (pintype "passive"))
    )
    (net (code "83") (name "unconnected-(D25-Pad-)") (class "Default")
      (node (ref "D25") (pin "-") (pinfunction "-_-") (pintype "passive"))
    )
    (net (code "84") (name "unconnected-(ERQWEWEW-Pad1)") (class "Default")
      (node (ref "ERQWEWEW") (pin "1") (pinfunction "1_1") (pintype "passive"))
    )
    (net (code "85") (name "unconnected-(ERQWEWEW-Pad2)") (class "Default")
      (node (ref "ERQWEWEW") (pin "2") (pinfunction "2_2") (pintype "passive"))
    )
    (net (code "86") (name "unconnected-(ERQWEWEW-Pad3)") (class "Default")
      (node (ref "ERQWEWEW") (pin "3") (pinfunction "3_3") (pintype "passive"))
    )
    (net (code "87") (name "unconnected-(ERQWEWEW-Pad4)") (class "Default")
      (node (ref "ERQWEWEW") (pin "4") (pinfunction "4_4") (pintype "passive"))
    )
    (net (code "88") (name "unconnected-(ERQWEWEW-Pad5)") (class "Default")
      (node (ref "ERQWEWEW") (pin "5") (pinfunction "5_5") (pintype "passive"))
    )
    (net (code "89") (name "unconnected-(ERQWEWEW-Pad6)") (class "Default")
      (node (ref "ERQWEWEW") (pin "6") (pinfunction "6_6") (pintype "passive"))
    )
    (net (code "90") (name "unconnected-(ERQWEWEW-Pad7)") (class "Default")
      (node (ref "ERQWEWEW") (pin "7") (pinfunction "7_7") (pintype "passive"))
    )
    (net (code "91") (name "unconnected-(ERQWEWEW-Pad8)") (class "Default")
      (node (ref "ERQWEWEW") (pin "8") (pinfunction "8_8") (pintype "passive"))
    )
    (net (code "92") (name "unconnected-(ERQWEWEW-Pad9)") (class "Default")
      (node (ref "ERQWEWEW") (pin "9") (pinfunction "9_9") (pintype "passive"))
    )
    (net (code "93") (name "unconnected-(ERQWEWEW-Pad10)") (class "Default")
      (node (ref "ERQWEWEW") (pin "10") (pinfunction "10_10") (pintype "passive"))
    )
    (net (code "94") (name "unconnected-(GHBGBHG-Pad1)") (class "Default")
      (node (ref "GHBGBHG") (pin "1") (pinfunction "1_1") (pintype "passive"))
    )
    (net (code "95") (name "unconnected-(GHBGBHG-Pad2)") (class "Default")
      (node (ref "GHBGBHG") (pin "2") (pinfunction "2_2") (pintype "passive"))
    )
    (net (code "96") (name "unconnected-(GHBGBHG-Pad3)") (class "Default")
      (node (ref "GHBGBHG") (pin "3") (pinfunction "3_3") (pintype "passive"))
    )
    (net (code "97") (name "unconnected-(GHBGBHG-Pad4)") (class "Default")
      (node (ref "GHBGBHG") (pin "4") (pinfunction "4_4") (pintype "passive"))
    )
    (net (code "98") (name "unconnected-(GHBGBHG-Pad5)") (class "Default")
      (node (ref "GHBGBHG") (pin "5") (pinfunction "5_5") (pintype "passive"))
    )
    (net (code "99") (name "unconnected-(GHBGBHG-Pad6)") (class "Default")
      (node (ref "GHBGBHG") (pin "6") (pinfunction "6_6") (pintype "passive"))
    )
    (net (code "100") (name "unconnected-(GHBGBHG-Pad7)") (class "Default")
      (node (ref "GHBGBHG") (pin "7") (pinfunction "7_7") (pintype "passive"))
    )
    (net (code "101") (name "unconnected-(GHBGBHG-Pad8)") (class "Default")
      (node (ref "GHBGBHG") (pin "8") (pinfunction "8_8") (pintype "passive"))
    )
    (net (code "102") (name "unconnected-(GHBGBHG-Pad9)") (class "Default")
      (node (ref "GHBGBHG") (pin "9") (pinfunction "9_9") (pintype "passive"))
    )
    (net (code "103") (name "unconnected-(GHBGBHG-Pad10)") (class "Default")
      (node (ref "GHBGBHG") (pin "10") (pinfunction "10_10") (pintype "passive"))
    )
    (net (code "104") (name "unconnected-(IC1-Pad2)") (class "Default")
      (node (ref "IC1") (pin "2") (pinfunction "2_2") (pintype "passive"))
    )
    (net (code "105") (name "unconnected-(IC1-Pad3)") (class "Default")
      (node (ref "IC1") (pin "3") (pinfunction "3_3") (pintype "passive"))
    )
    (net (code "106") (name "unconnected-(IC1-Pad4)") (class "Default")
      (node (ref "IC1") (pin "4") (pinfunction "4_4") (pintype "passive"))
    )
    (net (code "107") (name "unconnected-(IC1-Pad5)") (class "Default")
      (node (ref "IC1") (pin "5") (pinfunction "5_5") (pintype "passive"))
    )
    (net (code "108") (name "unconnected-(IC1-Pad6)") (class "Default")
      (node (ref "IC1") (pin "6") (pinfunction "6_6") (pintype "passive"))
    )
    (net (code "109") (name "unconnected-(IC1-Pad7)") (class "Default")
      (node (ref "IC1") (pin "7") (pinfunction "7_7") (pintype "passive"))
    )
    (net (code "110") (name "unconnected-(IC1-Pad8)") (class "Default")
      (node (ref "IC1") (pin "8") (pinfunction "8_8") (pintype "passive"))
    )
    (net (code "111") (name "unconnected-(IC1-Pad9)") (class "Default")
      (node (ref "IC1") (pin "9") (pinfunction "9_9") (pintype "passive"))
    )
    (net (code "112") (name "unconnected-(IC1-Pad10)") (class "Default")
      (node (ref "IC1") (pin "10") (pinfunction "10_10") (pintype "passive"))
    )
    (net (code "113") (name "unconnected-(IC1-Pad11)") (class "Default")
      (node (ref "IC1") (pin "11") (pinfunction "11_11") (pintype "passive"))
    )
    (net (code "114") (name "unconnected-(IC1-Pad12)") (class "Default")
      (node (ref "IC1") (pin "12") (pinfunction "12_12") (pintype "passive"))
    )
    (net (code "115") (name "unconnected-(IC1-Pad13)") (class "Default")
      (node (ref "IC1") (pin "13") (pinfunction "13_13") (pintype "passive"))
    )
    (net (code "116") (name "unconnected-(IC1-Pad14)") (class "Default")
      (node (ref "IC1") (pin "14") (pinfunction "14_14") (pintype "passive"))
    )
    (net (code "117") (name "unconnected-(IC1-Pad15)") (class "Default")
      (node (ref "IC1") (pin "15") (pinfunction "15_15") (pintype "passive"))
    )
    (net (code "118") (name "unconnected-(IC1-Pad16)") (class "Default")
      (node (ref "IC1") (pin "16") (pinfunction "16_16") (pintype "passive"))
    )
    (net (code "119") (name "unconnected-(IC1-Pad17)") (class "Default")
      (node (ref "IC1") (pin "17") (pinfunction "17_17") (pintype "passive"))
    )
    (net (code "120") (name "unconnected-(IC1-Pad18)") (class "Default")
      (node (ref "IC1") (pin "18") (pinfunction "18_18") (pintype "passive"))
    )
    (net (code "121") (name "unconnected-(IC1-Pad19)") (class "Default")
      (node (ref "IC1") (pin "19") (pinfunction "19_19") (pintype "passive"))
    )
    (net (code "122") (name "unconnected-(IC1-Pad20)") (class "Default")
      (node (ref "IC1") (pin "20") (pinfunction "20_20") (pintype "passive"))
    )
    (net (code "123") (name "unconnected-(IC1-Pad21)") (class "Default")
      (node (ref "IC1") (pin "21") (pinfunction "21_21") (pintype "passive"))
    )
    (net (code "124") (name "unconnected-(IC1-Pad22)") (class "Default")
      (node (ref "IC1") (pin "22") (pinfunction "22_22") (pintype "passive"))
    )
    (net (code "125") (name "unconnected-(IC1-Pad23)") (class "Default")
      (node (ref "IC1") (pin "23") (pinfunction "23_23") (pintype "passive"))
    )
    (net (code "126") (name "unconnected-(IC1-Pad24)") (class "Default")
      (node (ref "IC1") (pin "24") (pinfunction "24_24") (pintype "passive"))
    )
    (net (code "127") (name "unconnected-(IC1-Pad25)") (class "Default")
      (node (ref "IC1") (pin "25") (pinfunction "25_25") (pintype "passive"))
    )
    (net (code "128") (name "unconnected-(IC1-Pad26)") (class "Default")
      (node (ref "IC1") (pin "26") (pinfunction "26_26") (pintype "passive"))
    )
    (net (code "129") (name "unconnected-(IC1-Pad27)") (class "Default")
      (node (ref "IC1") (pin "27") (pinfunction "27_27") (pintype "passive"))
    )
    (net (code "130") (name "unconnected-(IC1-Pad28)") (class "Default")
      (node (ref "IC1") (pin "28") (pinfunction "28_28") (pintype "passive"))
    )
    (net (code "131") (name "unconnected-(IC2-Pad1)") (class "Default")
      (node (ref "IC2") (pin "1") (pinfunction "1_1") (pintype "bidirectional"))
    )
    (net (code "132") (name "unconnected-(IC2-Pad2)") (class "Default")
      (node (ref "IC2") (pin "2") (pinfunction "2_2") (pintype "bidirectional"))
    )
    (net (code "133") (name "unconnected-(IC2-Pad3)") (class "Default")
      (node (ref "IC2") (pin "3") (pinfunction "3_3") (pintype "bidirectional"))
    )
    (net (code "134") (name "unconnected-(IC2-Pad4)") (class "Default")
      (node (ref "IC2") (pin "4") (pinfunction "4_4") (pintype "bidirectional"))
    )
    (net (code "135") (name "unconnected-(IC2-Pad5)") (class "Default")
      (node (ref "IC2") (pin "5") (pinfunction "5_5") (pintype "bidirectional"))
    )
    (net (code "136") (name "unconnected-(IC2-Pad6)") (class "Default")
      (node (ref "IC2") (pin "6") (pinfunction "6_6") (pintype "bidirectional"))
    )
    (net (code "137") (name "unconnected-(IC2-Pad7)") (class "Default")
      (node (ref "IC2") (pin "7") (pinfunction "7_7") (pintype "bidirectional"))
    )
    (net (code "138") (name "unconnected-(IC2-Pad8)") (class "Default")
      (node (ref "IC2") (pin "8") (pinfunction "8_8") (pintype "bidirectional"))
    )
    (net (code "139") (name "unconnected-(IC2-Pad9)") (class "Default")
      (node (ref "IC2") (pin "9") (pinfunction "9_9") (pintype "bidirectional"))
    )
    (net (code "140") (name "unconnected-(IC2-Pad10)") (class "Default")
      (node (ref "IC2") (pin "10") (pinfunction "10_10") (pintype "bidirectional"))
    )
    (net (code "141") (name "unconnected-(IC2-Pad11)") (class "Default")
      (node (ref "IC2") (pin "11") (pinfunction "11_11") (pintype "bidirectional"))
    )
    (net (code "142") (name "unconnected-(IC2-Pad12)") (class "Default")
      (node (ref "IC2") (pin "12") (pinfunction "12_12") (pintype "bidirectional"))
    )
    (net (code "143") (name "unconnected-(IC2-Pad13)") (class "Default")
      (node (ref "IC2") (pin "13") (pinfunction "13_13") (pintype "bidirectional"))
    )
    (net (code "144") (name "unconnected-(IC2-Pad14)") (class "Default")
      (node (ref "IC2") (pin "14") (pinfunction "14_14") (pintype "bidirectional"))
    )
    (net (code "145") (name "unconnected-(IC2-Pad15)") (class "Default")
      (node (ref "IC2") (pin "15") (pinfunction "15_15") (pintype "bidirectional"))
    )
    (net (code "146") (name "unconnected-(IC2-Pad16)") (class "Default")
      (node (ref "IC2") (pin "16") (pinfunction "16_16") (pintype "bidirectional"))
    )
    (net (code "147") (name "unconnected-(IC3-P$1-Pad1)") (class "Default")
      (node (ref "IC3") (pin "1") (pinfunction "P$1_1") (pintype "bidirectional"))
    )
    (net (code "148") (name "unconnected-(IC3-P$2-Pad2)") (class "Default")
      (node (ref "IC3") (pin "2") (pinfunction "P$2_2") (pintype "bidirectional"))
    )
    (net (code "149") (name "unconnected-(IC3-P$3-Pad3)") (class "Default")
      (node (ref "IC3") (pin "3") (pinfunction "P$3_3") (pintype "bidirectional"))
    )
    (net (code "150") (name "unconnected-(IC3-P$4-Pad4)") (class "Default")
      (node (ref "IC3") (pin "4") (pinfunction "P$4_4") (pintype "bidirectional"))
    )
    (net (code "151") (name "unconnected-(IC3-P$5-Pad5)") (class "Default")
      (node (ref "IC3") (pin "5") (pinfunction "P$5_5") (pintype "bidirectional"))
    )
    (net (code "152") (name "unconnected-(IC3-P$6-Pad6)") (class "Default")
      (node (ref "IC3") (pin "6") (pinfunction "P$6_6") (pintype "bidirectional"))
    )
    (net (code "153") (name "unconnected-(IC3-P$7-Pad7)") (class "Default")
      (node (ref "IC3") (pin "7") (pinfunction "P$7_7") (pintype "bidirectional"))
    )
    (net (code "154") (name "unconnected-(IC3-P$8-Pad8)") (class "Default")
      (node (ref "IC3") (pin "8") (pinfunction "P$8_8") (pintype "bidirectional"))
    )
    (net (code "155") (name "unconnected-(IC3-P$9-Pad9)") (class "Default")
      (node (ref "IC3") (pin "9") (pinfunction "P$9_9") (pintype "bidirectional"))
    )
    (net (code "156") (name "unconnected-(IC3-P$10-Pad10)") (class "Default")
      (node (ref "IC3") (pin "10") (pinfunction "P$10_10") (pintype "bidirectional"))
    )
    (net (code "157") (name "unconnected-(IC3-P$11-Pad11)") (class "Default")
      (node (ref "IC3") (pin "11") (pinfunction "P$11_11") (pintype "bidirectional"))
    )
    (net (code "158") (name "unconnected-(IC3-P$12-Pad12)") (class "Default")
      (node (ref "IC3") (pin "12") (pinfunction "P$12_12") (pintype "bidirectional"))
    )
    (net (code "159") (name "unconnected-(IC3-P$13-Pad13)") (class "Default")
      (node (ref "IC3") (pin "13") (pinfunction "P$13_13") (pintype "bidirectional"))
    )
    (net (code "160") (name "unconnected-(IC3-P$14-Pad14)") (class "Default")
      (node (ref "IC3") (pin "14") (pinfunction "P$14_14") (pintype "bidirectional"))
    )
    (net (code "161") (name "unconnected-(IC3-P$15-Pad15)") (class "Default")
      (node (ref "IC3") (pin "15") (pinfunction "P$15_15") (pintype "bidirectional"))
    )
    (net (code "162") (name "unconnected-(IC3-P$16-Pad16)") (class "Default")
      (node (ref "IC3") (pin "16") (pinfunction "P$16_16") (pintype "bidirectional"))
    )
    (net (code "163") (name "unconnected-(IC3-P$17-Pad17)") (class "Default")
      (node (ref "IC3") (pin "17") (pinfunction "P$17_17") (pintype "bidirectional"))
    )
    (net (code "164") (name "unconnected-(IC3-P$18-Pad18)") (class "Default")
      (node (ref "IC3") (pin "18") (pinfunction "P$18_18") (pintype "bidirectional"))
    )
    (net (code "165") (name "unconnected-(J1---Pad-1)") (class "Default")
      (node (ref "J1") (pin "-1") (pinfunction "-_-1") (pintype "bidirectional"))
    )
    (net (code "166") (name "unconnected-(J1-CDN-Pad-2)") (class "Default")
      (node (ref "J1") (pin "-2") (pinfunction "CDN_-2") (pintype "bidirectional"))
    )
    (net (code "167") (name "unconnected-(J1-Pad+)") (class "Default")
      (node (ref "J1") (pin "+") (pinfunction "+_+") (pintype "bidirectional"))
    )
    (net (code "168") (name "unconnected-(JP1-Pad1)") (class "Default")
      (node (ref "JP1") (pin "1") (pinfunction "1_1") (pintype "passive"))
    )
    (net (code "169") (name "unconnected-(JP1-Pad2)") (class "Default")
      (node (ref "JP1") (pin "2") (pinfunction "2_2") (pintype "passive"))
    )
    (net (code "170") (name "unconnected-(JP1-Pad3)") (class "Default")
      (node (ref "JP1") (pin "3") (pinfunction "3_3") (pintype "passive"))
    )
    (net (code "171") (name "unconnected-(JP1-Pad4)") (class "Default")
      (node (ref "JP1") (pin "4") (pinfunction "4_4") (pintype "passive"))
    )
    (net (code "172") (name "unconnected-(JP1-Pad5)") (class "Default")
      (node (ref "JP1") (pin "5") (pinfunction "5_5") (pintype "passive"))
    )
    (net (code "173") (name "unconnected-(JP1-Pad6)") (class "Default")
      (node (ref "JP1") (pin "6") (pinfunction "6_6") (pintype "passive"))
    )
    (net (code "174") (name "unconnected-(JP2-Pad1)") (class "Default")
      (node (ref "JP2") (pin "1") (pinfunction "1_1") (pintype "passive"))
    )
    (net (code "175") (name "unconnected-(JP2-Pad2)") (class "Default")
      (node (ref "JP2") (pin "2") (pinfunction "2_2") (pintype "passive"))
    )
    (net (code "176") (name "unconnected-(JP2-Pad3)") (class "Default")
      (node (ref "JP2") (pin "3") (pinfunction "3_3") (pintype "passive"))
    )
    (net (code "177") (name "unconnected-(JP2-Pad4)") (class "Default")
      (node (ref "JP2") (pin "4") (pinfunction "4_4") (pintype "passive"))
    )
    (net (code "178") (name "unconnected-(JP2-Pad5)") (class "Default")
      (node (ref "JP2") (pin "5") (pinfunction "5_5") (pintype "passive"))
    )
    (net (code "179") (name "unconnected-(JP2-Pad6)") (class "Default")
      (node (ref "JP2") (pin "6") (pinfunction "6_6") (pintype "passive"))
    )
    (net (code "180") (name "unconnected-(JP3-Pad1)") (class "Default")
      (node (ref "JP3") (pin "1") (pinfunction "1_1") (pintype "passive"))
    )
    (net (code "181") (name "unconnected-(JP3-Pad2)") (class "Default")
      (node (ref "JP3") (pin "2") (pinfunction "2_2") (pintype "passive"))
    )
    (net (code "182") (name "unconnected-(JP3-Pad3)") (class "Default")
      (node (ref "JP3") (pin "3") (pinfunction "3_3") (pintype "passive"))
    )
    (net (code "183") (name "unconnected-(JP3-Pad4)") (class "Default")
      (node (ref "JP3") (pin "4") (pinfunction "4_4") (pintype "passive"))
    )
    (net (code "184") (name "unconnected-(JP3-Pad5)") (class "Default")
      (node (ref "JP3") (pin "5") (pinfunction "5_5") (pintype "passive"))
    )
    (net (code "185") (name "unconnected-(JP3-Pad6)") (class "Default")
      (node (ref "JP3") (pin "6") (pinfunction "6_6") (pintype "passive"))
    )
    (net (code "186") (name "unconnected-(JP4-Pad1)") (class "Default")
      (node (ref "JP4") (pin "1") (pinfunction "1_1") (pintype "passive"))
    )
    (net (code "187") (name "unconnected-(JP4-Pad2)") (class "Default")
      (node (ref "JP4") (pin "2") (pinfunction "2_2") (pintype "passive"))
    )
    (net (code "188") (name "unconnected-(JP4-Pad3)") (class "Default")
      (node (ref "JP4") (pin "3") (pinfunction "3_3") (pintype "passive"))
    )
    (net (code "189") (name "unconnected-(JP4-Pad4)") (class "Default")
      (node (ref "JP4") (pin "4") (pinfunction "4_4") (pintype "passive"))
    )
    (net (code "190") (name "unconnected-(JP4-Pad5)") (class "Default")
      (node (ref "JP4") (pin "5") (pinfunction "5_5") (pintype "passive"))
    )
    (net (code "191") (name "unconnected-(JP4-Pad6)") (class "Default")
      (node (ref "JP4") (pin "6") (pinfunction "6_6") (pintype "passive"))
    )
    (net (code "192") (name "unconnected-(JP5-Pad1)") (class "Default")
      (node (ref "JP5") (pin "1") (pinfunction "1_1") (pintype "passive"))
    )
    (net (code "193") (name "unconnected-(JP5-Pad2)") (class "Default")
      (node (ref "JP5") (pin "2") (pinfunction "2_2") (pintype "passive"))
    )
    (net (code "194") (name "unconnected-(JP5-Pad3)") (class "Default")
      (node (ref "JP5") (pin "3") (pinfunction "3_3") (pintype "passive"))
    )
    (net (code "195") (name "unconnected-(JP5-Pad4)") (class "Default")
      (node (ref "JP5") (pin "4") (pinfunction "4_4") (pintype "passive"))
    )
    (net (code "196") (name "unconnected-(JP5-Pad5)") (class "Default")
      (node (ref "JP5") (pin "5") (pinfunction "5_5") (pintype "passive"))
    )
    (net (code "197") (name "unconnected-(JP5-Pad6)") (class "Default")
      (node (ref "JP5") (pin "6") (pinfunction "6_6") (pintype "passive"))
    )
    (net (code "198") (name "unconnected-(JP6-Pad1)") (class "Default")
      (node (ref "JP6") (pin "1") (pinfunction "1_1") (pintype "passive"))
    )
    (net (code "199") (name "unconnected-(JP6-Pad2)") (class "Default")
      (node (ref "JP6") (pin "2") (pinfunction "2_2") (pintype "passive"))
    )
    (net (code "200") (name "unconnected-(JP6-Pad3)") (class "Default")
      (node (ref "JP6") (pin "3") (pinfunction "3_3") (pintype "passive"))
    )
    (net (code "201") (name "unconnected-(JP6-Pad4)") (class "Default")
      (node (ref "JP6") (pin "4") (pinfunction "4_4") (pintype "passive"))
    )
    (net (code "202") (name "unconnected-(JP6-Pad5)") (class "Default")
      (node (ref "JP6") (pin "5") (pinfunction "5_5") (pintype "passive"))
    )
    (net (code "203") (name "unconnected-(JP6-Pad6)") (class "Default")
      (node (ref "JP6") (pin "6") (pinfunction "6_6") (pintype "passive"))
    )
    (net (code "204") (name "unconnected-(L1-Pad1)") (class "Default")
      (node (ref "L1") (pin "1") (pinfunction "1_1") (pintype "passive"))
    )
    (net (code "205") (name "unconnected-(L1-Pad2)") (class "Default")
      (node (ref "L1") (pin "2") (pinfunction "2_2") (pintype "passive"))
    )
    (net (code "206") (name "unconnected-(R1-Pad1)") (class "Default")
      (node (ref "R1") (pin "1") (pinfunction "1_1") (pintype "passive"))
    )
    (net (code "207") (name "unconnected-(R1-Pad2)") (class "Default")
      (node (ref "R1") (pin "2") (pinfunction "2_2") (pintype "passive"))
    )
    (net (code "208") (name "unconnected-(R2-Pad1)") (class "Default")
      (node (ref "R2") (pin "1") (pinfunction "1_1") (pintype "passive"))
    )
    (net (code "209") (name "unconnected-(R2-Pad2)") (class "Default")
      (node (ref "R2") (pin "2") (pinfunction "2_2") (pintype "passive"))
    )
    (net (code "210") (name "unconnected-(R3-Pad1)") (class "Default")
      (node (ref "R3") (pin "1") (pinfunction "1_1") (pintype "passive"))
    )
    (net (code "211") (name "unconnected-(R3-Pad2)") (class "Default")
      (node (ref "R3") (pin "2") (pinfunction "2_2") (pintype "passive"))
    )
    (net (code "212") (name "unconnected-(R4-Pad1)") (class "Default")
      (node (ref "R4") (pin "1") (pinfunction "1_1") (pintype "passive"))
    )
    (net (code "213") (name "unconnected-(R4-Pad2)") (class "Default")
      (node (ref "R4") (pin "2") (pinfunction "2_2") (pintype "passive"))
    )
    (net (code "214") (name "unconnected-(R5-Pad1)") (class "Default")
      (node (ref "R5") (pin "1") (pinfunction "1_1") (pintype "passive"))
    )
    (net (code "215") (name "unconnected-(R5-Pad2)") (class "Default")
      (node (ref "R5") (pin "2") (pinfunction "2_2") (pintype "passive"))
    )
    (net (code "216") (name "unconnected-(R6-Pad1)") (class "Default")
      (node (ref "R6") (pin "1") (pinfunction "1_1") (pintype "passive"))
    )
    (net (code "217") (name "unconnected-(R6-Pad2)") (class "Default")
      (node (ref "R6") (pin "2") (pinfunction "2_2") (pintype "passive"))
    )
    (net (code "218") (name "unconnected-(R7-Pad1)") (class "Default")
      (node (ref "R7") (pin "1") (pinfunction "1_1") (pintype "passive"))
    )
    (net (code "219") (name "unconnected-(R7-Pad2)") (class "Default")
      (node (ref "R7") (pin "2") (pinfunction "2_2") (pintype "passive"))
    )
    (net (code "220") (name "unconnected-(R8-Pad1)") (class "Default")
      (node (ref "R8") (pin "1") (pinfunction "1_1") (pintype "passive"))
    )
    (net (code "221") (name "unconnected-(R8-Pad2)") (class "Default")
      (node (ref "R8") (pin "2") (pinfunction "2_2") (pintype "passive"))
    )
    (net (code "222") (name "unconnected-(R9-Pad1)") (class "Default")
      (node (ref "R9") (pin "1") (pinfunction "1_1") (pintype "passive"))
    )
    (net (code "223") (name "unconnected-(R9-Pad2)") (class "Default")
      (node (ref "R9") (pin "2") (pinfunction "2_2") (pintype "passive"))
    )
    (net (code "224") (name "unconnected-(R10-Pad1)") (class "Default")
      (node (ref "R10") (pin "1") (pinfunction "1_1") (pintype "passive"))
    )
    (net (code "225") (name "unconnected-(R10-Pad2)") (class "Default")
      (node (ref "R10") (pin "2") (pinfunction "2_2") (pintype "passive"))
    )
    (net (code "226") (name "unconnected-(R14-Pad1)") (class "Default")
      (node (ref "R14") (pin "1") (pinfunction "1_1") (pintype "passive"))
    )
    (net (code "227") (name "unconnected-(R14-Pad2)") (class "Default")
      (node (ref "R14") (pin "2") (pinfunction "2_2") (pintype "passive"))
    )
    (net (code "228") (name "unconnected-(R15-Pad1)") (class "Default")
      (node (ref "R15") (pin "1") (pinfunction "1_1") (pintype "passive"))
    )
    (net (code "229") (name "unconnected-(R15-Pad2)") (class "Default")
      (node (ref "R15") (pin "2") (pinfunction "2_2") (pintype "passive"))
    )
    (net (code "230") (name "unconnected-(R16-Pad1)") (class "Default")
      (node (ref "R16") (pin "1") (pinfunction "1_1") (pintype "passive"))
    )
    (net (code "231") (name "unconnected-(R16-Pad2)") (class "Default")
      (node (ref "R16") (pin "2") (pinfunction "2_2") (pintype "passive"))
    )
    (net (code "232") (name "unconnected-(R17-Pad1)") (class "Default")
      (node (ref "R17") (pin "1") (pinfunction "1_1") (pintype "passive"))
    )
    (net (code "233") (name "unconnected-(R17-Pad2)") (class "Default")
      (node (ref "R17") (pin "2") (pinfunction "2_2") (pintype "passive"))
    )
    (net (code "234") (name "unconnected-(R18-Pad1)") (class "Default")
      (node (ref "R18") (pin "1") (pinfunction "1_1") (pintype "passive"))
    )
    (net (code "235") (name "unconnected-(R18-Pad2)") (class "Default")
      (node (ref "R18") (pin "2") (pinfunction "2_2") (pintype "passive"))
    )
    (net (code "236") (name "unconnected-(R19-Pad1)") (class "Default")
      (node (ref "R19") (pin "1") (pinfunction "1_1") (pintype "passive"))
    )
    (net (code "237") (name "unconnected-(R19-Pad2)") (class "Default")
      (node (ref "R19") (pin "2") (pinfunction "2_2") (pintype "passive"))
    )
    (net (code "238") (name "unconnected-(R20-Pad1)") (class "Default")
      (node (ref "R20") (pin "1") (pinfunction "1_1") (pintype "passive"))
    )
    (net (code "239") (name "unconnected-(R20-Pad2)") (class "Default")
      (node (ref "R20") (pin "2") (pinfunction "2_2") (pintype "passive"))
    )
    (net (code "240") (name "unconnected-(R21-Pad1)") (class "Default")
      (node (ref "R21") (pin "1") (pinfunction "1_1") (pintype "passive"))
    )
    (net (code "241") (name "unconnected-(R21-Pad2)") (class "Default")
      (node (ref "R21") (pin "2") (pinfunction "2_2") (pintype "passive"))
    )
    (net (code "242") (name "unconnected-(R22-Pad1)") (class "Default")
      (node (ref "R22") (pin "1") (pinfunction "1_1") (pintype "passive"))
    )
    (net (code "243") (name "unconnected-(R22-Pad2)") (class "Default")
      (node (ref "R22") (pin "2") (pinfunction "2_2") (pintype "passive"))
    )
    (net (code "244") (name "unconnected-(R23-Pad1)") (class "Default")
      (node (ref "R23") (pin "1") (pinfunction "1_1") (pintype "passive"))
    )
    (net (code "245") (name "unconnected-(R23-Pad2)") (class "Default")
      (node (ref "R23") (pin "2") (pinfunction "2_2") (pintype "passive"))
    )
    (net (code "246") (name "unconnected-(R24-Pad1)") (class "Default")
      (node (ref "R24") (pin "1") (pinfunction "1_1") (pintype "passive"))
    )
    (net (code "247") (name "unconnected-(R24-Pad2)") (class "Default")
      (node (ref "R24") (pin "2") (pinfunction "2_2") (pintype "passive"))
    )
    (net (code "248") (name "unconnected-(R25-Pad1)") (class "Default")
      (node (ref "R25") (pin "1") (pinfunction "1_1") (pintype "passive"))
    )
    (net (code "249") (name "unconnected-(R25-Pad2)") (class "Default")
      (node (ref "R25") (pin "2") (pinfunction "2_2") (pintype "passive"))
    )
    (net (code "250") (name "unconnected-(R26-Pad1)") (class "Default")
      (node (ref "R26") (pin "1") (pinfunction "1_1") (pintype "passive"))
    )
    (net (code "251") (name "unconnected-(R26-Pad2)") (class "Default")
      (node (ref "R26") (pin "2") (pinfunction "2_2") (pintype "passive"))
    )
    (net (code "252") (name "unconnected-(R27-Pad1)") (class "Default")
      (node (ref "R27") (pin "1") (pinfunction "1_1") (pintype "passive"))
    )
    (net (code "253") (name "unconnected-(R27-Pad2)") (class "Default")
      (node (ref "R27") (pin "2") (pinfunction "2_2") (pintype "passive"))
    )
    (net (code "254") (name "unconnected-(R28-Pad1)") (class "Default")
      (node (ref "R28") (pin "1") (pinfunction "1_1") (pintype "passive"))
    )
    (net (code "255") (name "unconnected-(R28-Pad2)") (class "Default")
      (node (ref "R28") (pin "2") (pinfunction "2_2") (pintype "passive"))
    )
    (net (code "256") (name "unconnected-(R29-Pad1)") (class "Default")
      (node (ref "R29") (pin "1") (pinfunction "1_1") (pintype "passive"))
    )
    (net (code "257") (name "unconnected-(R29-Pad2)") (class "Default")
      (node (ref "R29") (pin "2") (pinfunction "2_2") (pintype "passive"))
    )
    (net (code "258") (name "unconnected-(R30-Pad1)") (class "Default")
      (node (ref "R30") (pin "1") (pinfunction "1_1") (pintype "passive"))
    )
    (net (code "259") (name "unconnected-(R30-Pad2)") (class "Default")
      (node (ref "R30") (pin "2") (pinfunction "2_2") (pintype "passive"))
    )
    (net (code "260") (name "unconnected-(R31-Pad1)") (class "Default")
      (node (ref "R31") (pin "1") (pinfunction "1_1") (pintype "passive"))
    )
    (net (code "261") (name "unconnected-(R31-Pad2)") (class "Default")
      (node (ref "R31") (pin "2") (pinfunction "2_2") (pintype "passive"))
    )
    (net (code "262") (name "unconnected-(R32-Pad1)") (class "Default")
      (node (ref "R32") (pin "1") (pinfunction "1_1") (pintype "passive"))
    )
    (net (code "263") (name "unconnected-(R32-Pad2)") (class "Default")
      (node (ref "R32") (pin "2") (pinfunction "2_2") (pintype "passive"))
    )
    (net (code "264") (name "unconnected-(R33-Pad1)") (class "Default")
      (node (ref "R33") (pin "1") (pinfunction "1_1") (pintype "passive"))
    )
    (net (code "265") (name "unconnected-(R33-Pad2)") (class "Default")
      (node (ref "R33") (pin "2") (pinfunction "2_2") (pintype "passive"))
    )
    (net (code "266") (name "unconnected-(R34-Pad1)") (class "Default")
      (node (ref "R34") (pin "1") (pinfunction "1_1") (pintype "passive"))
    )
    (net (code "267") (name "unconnected-(R34-Pad2)") (class "Default")
      (node (ref "R34") (pin "2") (pinfunction "2_2") (pintype "passive"))
    )
    (net (code "268") (name "unconnected-(R35-Pad1)") (class "Default")
      (node (ref "R35") (pin "1") (pinfunction "1_1") (pintype "passive"))
    )
    (net (code "269") (name "unconnected-(R35-Pad2)") (class "Default")
      (node (ref "R35") (pin "2") (pinfunction "2_2") (pintype "passive"))
    )
    (net (code "270") (name "unconnected-(R36-Pad1)") (class "Default")
      (node (ref "R36") (pin "1") (pinfunction "1_1") (pintype "passive"))
    )
    (net (code "271") (name "unconnected-(R36-Pad2)") (class "Default")
      (node (ref "R36") (pin "2") (pinfunction "2_2") (pintype "passive"))
    )
    (net (code "272") (name "unconnected-(R37-Pad1)") (class "Default")
      (node (ref "R37") (pin "1") (pinfunction "1_1") (pintype "passive"))
    )
    (net (code "273") (name "unconnected-(R37-Pad2)") (class "Default")
      (node (ref "R37") (pin "2") (pinfunction "2_2") (pintype "passive"))
    )
    (net (code "274") (name "unconnected-(SW2-A1-Pad2)") (class "Default")
      (node (ref "SW2") (pin "2") (pinfunction "A1_2") (pintype "bidirectional"))
    )
    (net (code "275") (name "unconnected-(SW2-B1-Pad4)") (class "Default")
      (node (ref "SW2") (pin "4") (pinfunction "B1_4") (pintype "bidirectional"))
    )
    (net (code "276") (name "unconnected-(TGFGF-Pad1)") (class "Default")
      (node (ref "TGFGF") (pin "1") (pinfunction "1_1") (pintype "passive"))
    )
    (net (code "277") (name "unconnected-(TGFGF-Pad2)") (class "Default")
      (node (ref "TGFGF") (pin "2") (pinfunction "2_2") (pintype "passive"))
    )
    (net (code "278") (name "unconnected-(TGFGF-Pad3)") (class "Default")
      (node (ref "TGFGF") (pin "3") (pinfunction "3_3") (pintype "passive"))
    )
    (net (code "279") (name "unconnected-(TGFGF-Pad4)") (class "Default")
      (node (ref "TGFGF") (pin "4") (pinfunction "4_4") (pintype "passive"))
    )
    (net (code "280") (name "unconnected-(TGFGF-Pad5)") (class "Default")
      (node (ref "TGFGF") (pin "5") (pinfunction "5_5") (pintype "passive"))
    )
    (net (code "281") (name "unconnected-(TGFGF-Pad6)") (class "Default")
      (node (ref "TGFGF") (pin "6") (pinfunction "6_6") (pintype "passive"))
    )
    (net (code "282") (name "unconnected-(TGFGF-Pad7)") (class "Default")
      (node (ref "TGFGF") (pin "7") (pinfunction "7_7") (pintype "passive"))
    )
    (net (code "283") (name "unconnected-(TGFGF-Pad8)") (class "Default")
      (node (ref "TGFGF") (pin "8") (pinfunction "8_8") (pintype "passive"))
    )
    (net (code "284") (name "unconnected-(TGFGF-Pad9)") (class "Default")
      (node (ref "TGFGF") (pin "9") (pinfunction "9_9") (pintype "passive"))
    )
    (net (code "285") (name "unconnected-(TGFGF-Pad10)") (class "Default")
      (node (ref "TGFGF") (pin "10") (pinfunction "10_10") (pintype "passive"))
    )
    (net (code "286") (name "unconnected-(TGFGF-Pad11)") (class "Default")
      (node (ref "TGFGF") (pin "11") (pinfunction "11_11") (pintype "passive"))
    )
    (net (code "287") (name "unconnected-(TGFGF-Pad12)") (class "Default")
      (node (ref "TGFGF") (pin "12") (pinfunction "12_12") (pintype "passive"))
    )
    (net (code "288") (name "unconnected-(TGFGF-Pad13)") (class "Default")
      (node (ref "TGFGF") (pin "13") (pinfunction "13_13") (pintype "passive"))
    )
    (net (code "289") (name "unconnected-(TGFGF-Pad14)") (class "Default")
      (node (ref "TGFGF") (pin "14") (pinfunction "14_14") (pintype "passive"))
    )
  )
)
